# USB_OTG.net
KiCad netlist of a schematic drawn in Altium Designer
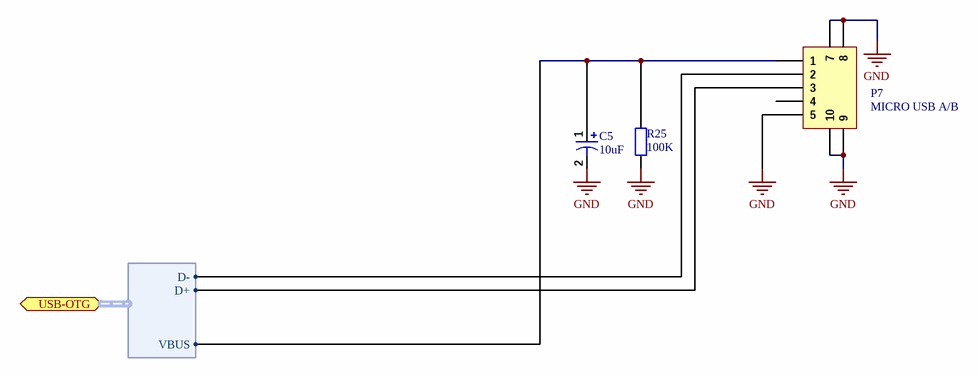
[diagram p0: USB OTG.SchDoc]

(export (version "E")
  (design (tool "Eeschema 10.0.6"))
  (components
    (comp (ref "C5")
      (value "10uF")
      (footprint "SYLANN:KEMET_4")
      (description "Polarized Capacitor")
      (fields
        (field (name "MANUFACTURER") "KEMET")
        (field (name "MANUFACTURER PART NUMBER") "EXV106M025A9BAA")
      )
      (libsource (lib "Miscellaneous Devices") (part "Cap Pol1"))
    )
    (comp (ref "P7")
      (value "MICRO USB A/B")
      (footprint "USB FCI 10104111")
      (description "Header, 5-Pin")
      (fields
        (field (name "MANUFACTURER") "FCI")
        (field (name "MANUFACTURER PART NUMBER") "10104111-0001LF")
        (field (name "PUBLISHER") "Altium Limited")
      )
      (libsource (lib "MAIN BOARD CERES") (part "Header 5"))
    )
    (comp (ref "R25")
      (value "100K")
      (footprint "R0805")
      (description "Resistor")
      (fields
        (field (name "MANUFACTURER") "MULTICOMP")
        (field (name "MANUFACTURER PART NUMBER") "MC0.1W08051%100KFR")
      )
      (libsource (lib "BRA") (part "Resistor 0805 100K"))
    )
  )
  (nets
    (net (code "2") (name "/D+") (class "Default")
      (node (ref "P7") (pin "3") (pinfunction "3_3") (pintype "passive"))
    )
    (net (code "3") (name "/D-") (class "Default")
      (node (ref "P7") (pin "2") (pinfunction "2_2") (pintype "passive"))
    )
    (net (code "4") (name "/VBUS") (class "Default")
      (node (ref "C5") (pin "1") (pinfunction "1_1") (pintype "passive"))
      (node (ref "P7") (pin "1") (pinfunction "1_1") (pintype "passive"))
      (node (ref "R25") (pin "2") (pinfunction "2_2") (pintype "passive"))
    )
    (net (code "6") (name "GND") (class "Default")
      (node (ref "C5") (pin "2") (pinfunction "2_2") (pintype "passive"))
      (node (ref "P7") (pin "10") (pinfunction "10_10") (pintype "passive"))
      (node (ref "P7") (pin "5") (pinfunction "5_5") (pintype "passive"))
      (node (ref "P7") (pin "7") (pinfunction "7_7") (pintype "passive"))
      (node (ref "P7") (pin "8") (pinfunction "8_8") (pintype "passive"))
      (node (ref "P7") (pin "9") (pinfunction "9_9") (pintype "passive"))
      (node (ref "R25") (pin "1") (pinfunction "1_1") (pintype "passive"))
    )
    (net (code "7") (name "unconnected-(P7-Pad4)") (class "Default")
      (node (ref "P7") (pin "4") (pinfunction "4_4") (pintype "passive"))
    )
  )
)
